# gyro.net
KiCad netlist of a schematic drawn in Altium Designer
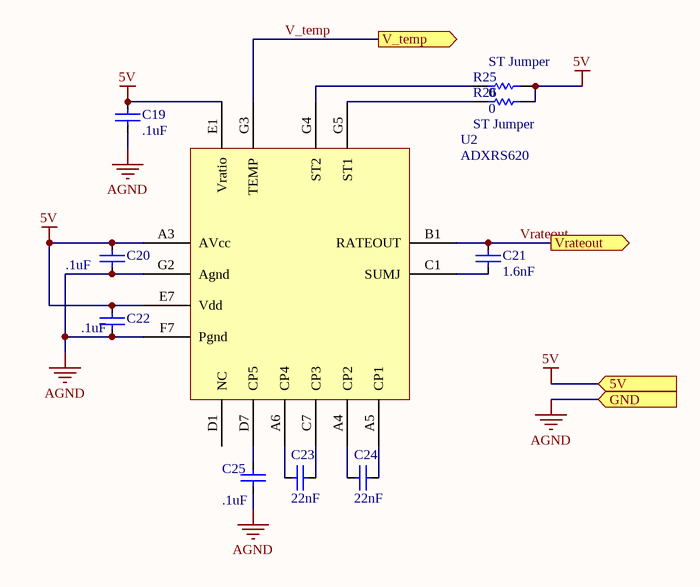
[diagram p0: gyro.SchDoc]

(export (version "E")
  (design (tool "Eeschema 10.0.6"))
  (components
    (comp (ref "C19")
      (value ".1uF")
      (footprint "0603 (1608)")
      (fields
        (field (name "MANUFACTURER") "Murata")
        (field (name "PART NO.") "490-1524-1-ND")
        (field (name "Comment") "Capacitor")
      )
      (libsource (lib "SMT Chip") (part "Capacitor"))
    )
    (comp (ref "C20")
      (value ".1uF")
      (footprint "0603 (1608)")
      (fields
        (field (name "MANUFACTURER") "Murata")
        (field (name "PART NO.") "490-1524-1-ND")
        (field (name "Comment") "Capacitor")
      )
      (libsource (lib "SMT Chip") (part "Capacitor"))
    )
    (comp (ref "C21")
      (value "1.6nF")
      (footprint "0603 (1608)")
      (fields
        (field (name "MANUFACTURER") "Murata")
        (field (name "PART NO.") "490-1456-1-ND")
        (field (name "Comment") "Capacitor")
      )
      (libsource (lib "SMT Chip") (part "Capacitor"))
    )
    (comp (ref "C22")
      (value ".1uF")
      (footprint "0603 (1608)")
      (fields
        (field (name "MANUFACTURER") "Murata")
        (field (name "PART NO.") "490-1524-1-ND")
        (field (name "Comment") "Capacitor")
      )
      (libsource (lib "SMT Chip") (part "Capacitor"))
    )
    (comp (ref "C23")
      (value "22nF")
      (footprint "0603 (1608)")
      (fields
        (field (name "MANUFACTURER") "TDK")
        (field (name "PART NO.") "445-5104-1-ND")
        (field (name "Comment") "Capacitor")
      )
      (libsource (lib "SMT Chip") (part "Capacitor"))
    )
    (comp (ref "C24")
      (value "22nF")
      (footprint "0603 (1608)")
      (fields
        (field (name "MANUFACTURER") "TDK")
        (field (name "PART NO.") "445-5104-1-ND")
        (field (name "Comment") "Capacitor")
      )
      (libsource (lib "SMT Chip") (part "Capacitor"))
    )
    (comp (ref "C25")
      (value ".1uF")
      (footprint "0603 (1608)")
      (fields
        (field (name "MANUFACTURER") "Murata")
        (field (name "PART NO.") "490-1524-1-ND")
        (field (name "Comment") "Capacitor")
      )
      (libsource (lib "SMT Chip") (part "Capacitor"))
    )
    (comp (ref "R25")
      (value "ST Jumper")
      (footprint "0603 (1608)")
      (description "Resistor")
      (fields (field (name "ALTIUM_VALUE") "0"))
      (libsource (lib "Miscellaneous Devices") (part "Res1"))
    )
    (comp (ref "R26")
      (value "ST Jumper")
      (footprint "0603 (1608)")
      (description "Resistor")
      (fields (field (name "ALTIUM_VALUE") "0"))
      (libsource (lib "Miscellaneous Devices") (part "Res1"))
    )
    (comp (ref "U2") (value "ADXRS620") (footprint "BGA_AXDR") (libsource (lib "imu") (part "ADXRS620")))
  )
  (nets
    (net (code "1") (name "/V_temp") (class "Default")
      (node (ref "U2") (pin "G3") (pinfunction "TEMP_G3") (pintype "passive"))
    )
    (net (code "2") (name "/Vrateout") (class "Default")
      (node (ref "C21") (pin "2") (pinfunction "2_2") (pintype "passive"))
      (node (ref "U2") (pin "B1") (pinfunction "RATEOUT_B1") (pintype "passive"))
    )
    (net (code "3") (name "5V") (class "Default")
      (node (ref "C19") (pin "1") (pinfunction "1_1") (pintype "passive"))
      (node (ref "C20") (pin "1") (pinfunction "1_1") (pintype "passive"))
      (node (ref "C22") (pin "1") (pinfunction "1_1") (pintype "passive"))
      (node (ref "R25") (pin "2") (pinfunction "2_2") (pintype "passive"))
      (node (ref "R26") (pin "2") (pinfunction "2_2") (pintype "passive"))
      (node (ref "U2") (pin "A3") (pinfunction "AVcc_A3") (pintype "passive"))
      (node (ref "U2") (pin "E1") (pinfunction "Vratio_E1") (pintype "passive"))
      (node (ref "U2") (pin "E7") (pinfunction "Vdd_E7") (pintype "passive"))
    )
    (net (code "4") (name "AGND") (class "Default")
      (node (ref "C19") (pin "2") (pinfunction "2_2") (pintype "passive"))
      (node (ref "C20") (pin "2") (pinfunction "2_2") (pintype "passive"))
      (node (ref "C22") (pin "2") (pinfunction "2_2") (pintype "passive"))
      (node (ref "C25") (pin "2") (pinfunction "2_2") (pintype "passive"))
      (node (ref "U2") (pin "F7") (pinfunction "Pgnd_F7") (pintype "passive"))
      (node (ref "U2") (pin "G2") (pinfunction "Agnd_G2") (pintype "passive"))
    )
    (net (code "5") (name "Net-(U2-CP1)") (class "Default")
      (node (ref "C24") (pin "2") (pinfunction "2_2") (pintype "passive"))
      (node (ref "U2") (pin "A5") (pinfunction "CP1_A5") (pintype "passive"))
    )
    (net (code "6") (name "Net-(U2-CP2)") (class "Default")
      (node (ref "C24") (pin "1") (pinfunction "1_1") (pintype "passive"))
      (node (ref "U2") (pin "A4") (pinfunction "CP2_A4") (pintype "passive"))
    )
    (net (code "7") (name "Net-(U2-CP3)") (class "Default")
      (node (ref "C23") (pin "2") (pinfunction "2_2") (pintype "passive"))
      (node (ref "U2") (pin "C7") (pinfunction "CP3_C7") (pintype "passive"))
    )
    (net (code "8") (name "Net-(U2-CP4)") (class "Default")
      (node (ref "C23") (pin "1") (pinfunction "1_1") (pintype "passive"))
      (node (ref "U2") (pin "A6") (pinfunction "CP4_A6") (pintype "passive"))
    )
    (net (code "9") (name "Net-(U2-CP5)") (class "Default")
      (node (ref "C25") (pin "1") (pinfunction "1_1") (pintype "passive"))
      (node (ref "U2") (pin "D7") (pinfunction "CP5_D7") (pintype "passive"))
    )
    (net (code "10") (name "Net-(U2-ST1)") (class "Default")
      (node (ref "R26") (pin "1") (pinfunction "1_1") (pintype "passive"))
      (node (ref "U2") (pin "G5") (pinfunction "ST1_G5") (pintype "passive"))
    )
    (net (code "11") (name "Net-(U2-ST2)") (class "Default")
      (node (ref "R25") (pin "1") (pinfunction "1_1") (pintype "passive"))
      (node (ref "U2") (pin "G4") (pinfunction "ST2_G4") (pintype "passive"))
    )
    (net (code "12") (name "Net-(U2-SUMJ)") (class "Default")
      (node (ref "C21") (pin "1") (pinfunction "1_1") (pintype "passive"))
      (node (ref "U2") (pin "C1") (pinfunction "SUMJ_C1") (pintype "passive"))
    )
    (net (code "13") (name "unconnected-(U2-NC-PadD1)") (class "Default")
      (node (ref "U2") (pin "D1") (pinfunction "NC_D1") (pintype "passive"))
    )
  )
)
